# RemoteSch.net
KiCad netlist of a schematic drawn in Altium Designer
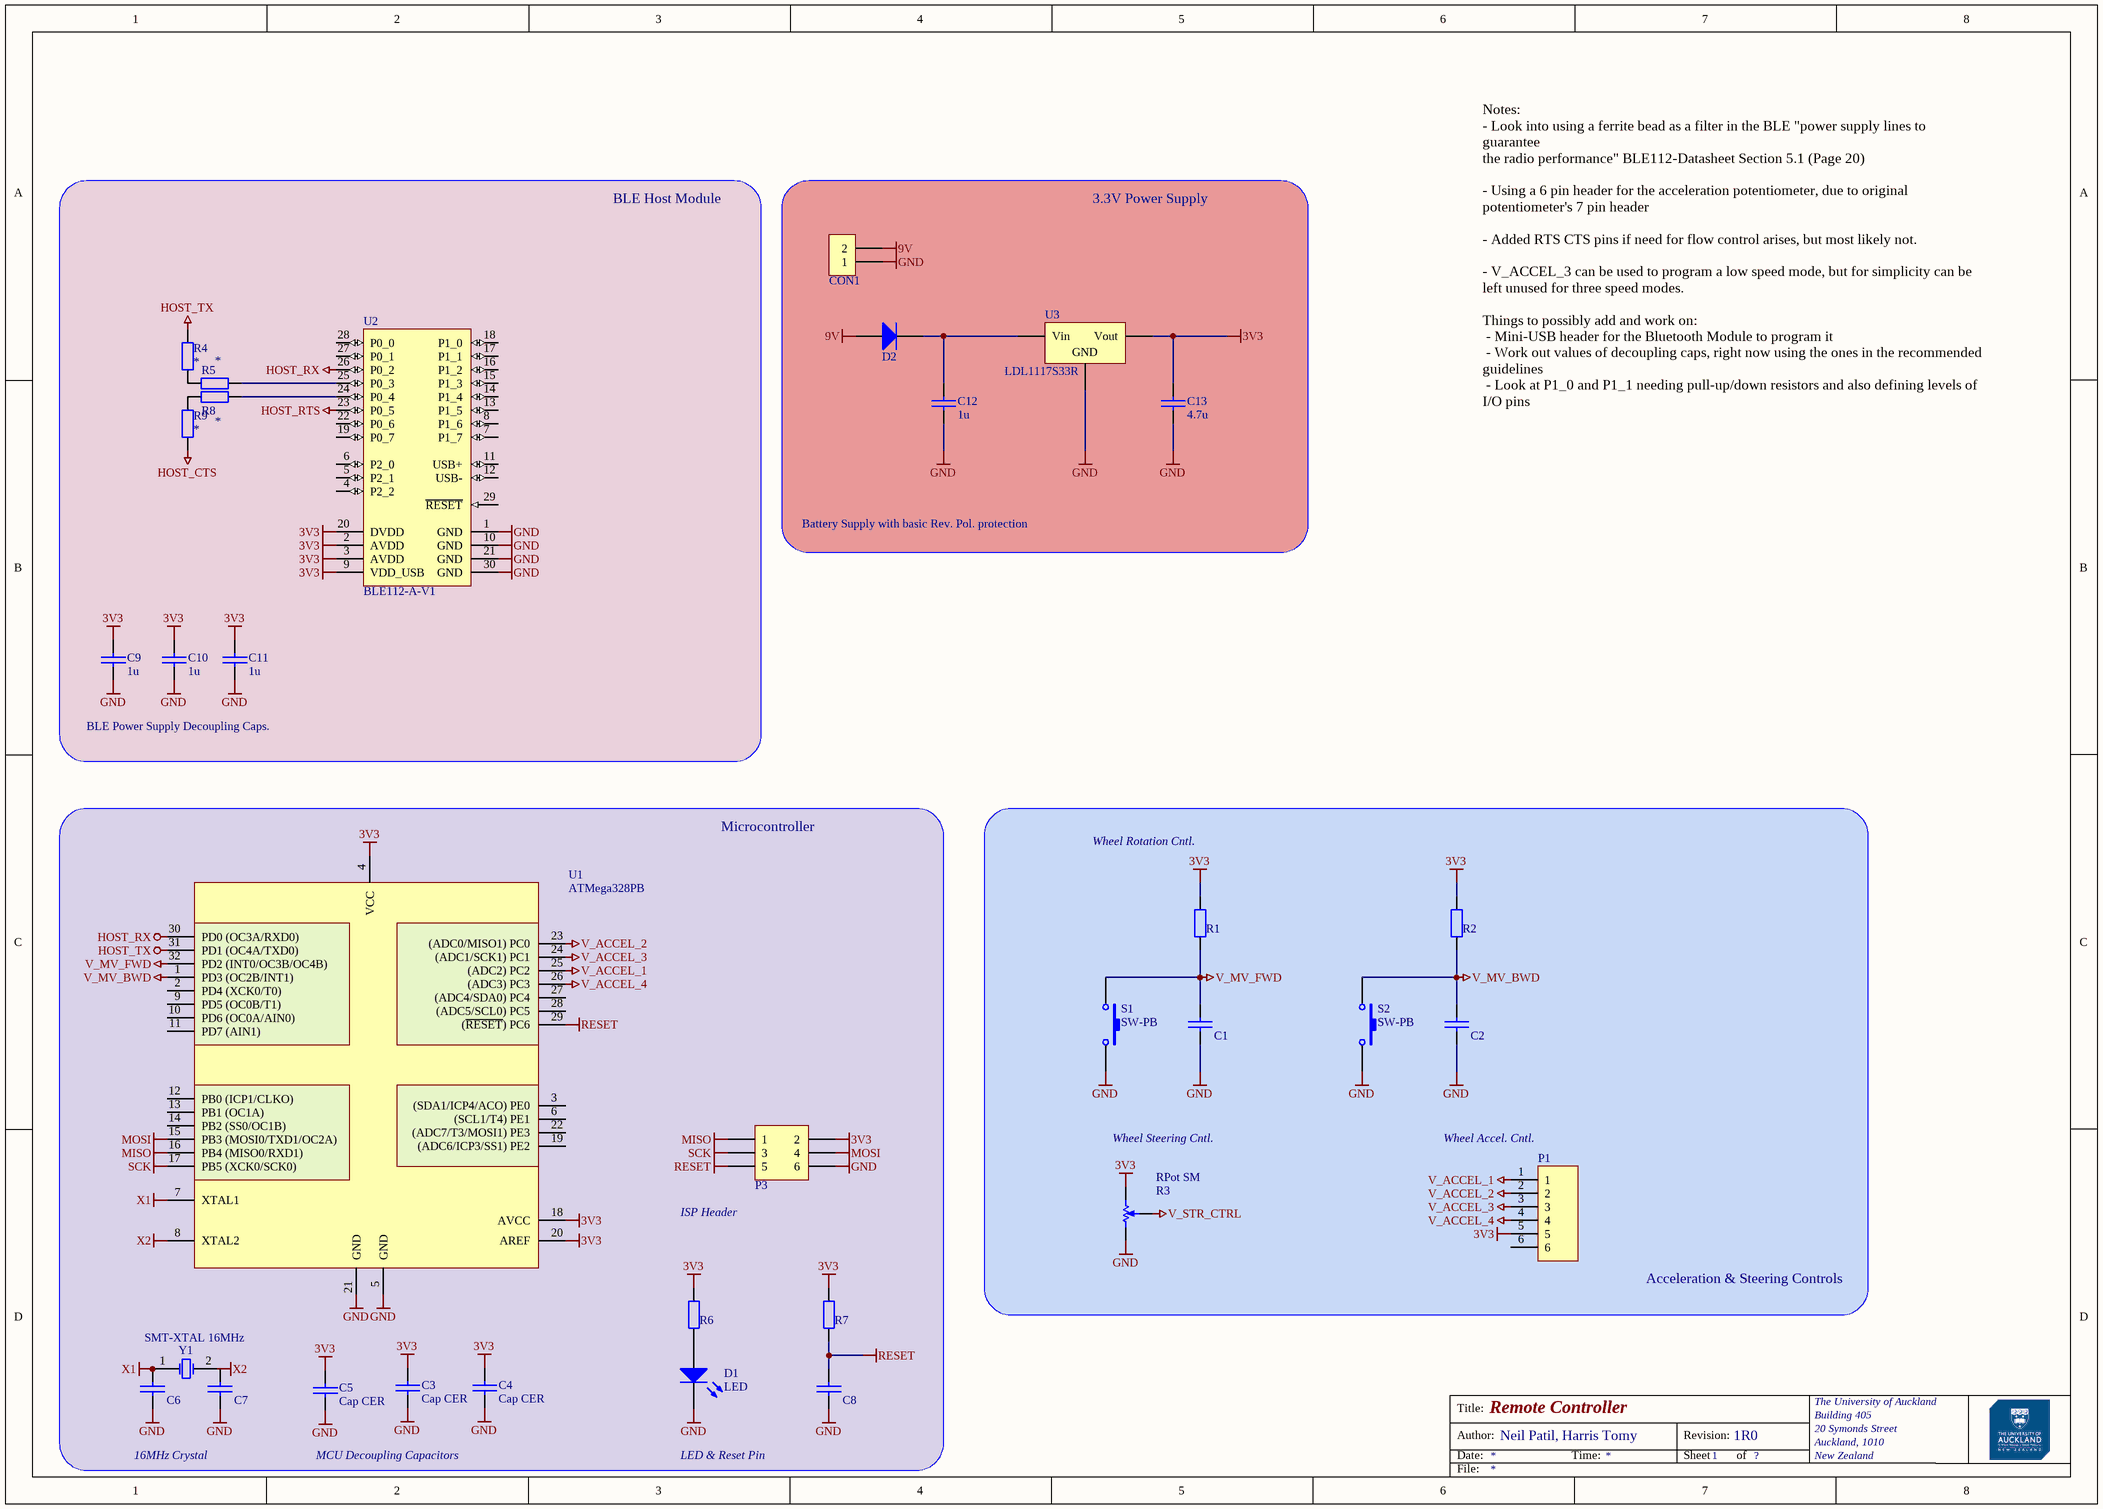
[diagram p0: RemoteSch.SchDoc]

(export (version "E")
  (design (tool "Eeschema 10.0.6"))
  (components
    (comp (ref "C1")
      (value "Capacitor 0805")
      (footprint "C0805")
      (description "CCAP0805")
      (libsource (lib "CommonDevices_V1") (part "CCAP0805"))
    )
    (comp (ref "C2")
      (value "Capacitor 0805")
      (footprint "C0805")
      (description "CCAP0805")
      (libsource (lib "CommonDevices_V1") (part "CCAP0805"))
    )
    (comp (ref "C3")
      (value "Cap CER")
      (footprint "C1206")
      (description "CAP CER 0.1UF 100V C0G 1206")
      (fields (field (name "MPN") "C3216C0G2A104J160AC") (field (name "MANUFACTURER") "TDK Corporation"))
      (libsource (lib "E209_Lib") (part "Cap CER Decoup C3216C0G2A104J160AC"))
    )
    (comp (ref "C4")
      (value "Cap CER")
      (footprint "C1206")
      (description "CAP CER 0.1UF 100V C0G 1206")
      (fields (field (name "MPN") "C3216C0G2A104J160AC") (field (name "MANUFACTURER") "TDK Corporation"))
      (libsource (lib "E209_Lib") (part "Cap CER Decoup C3216C0G2A104J160AC"))
    )
    (comp (ref "C5")
      (value "Cap CER")
      (footprint "C1206")
      (description "CAP CER 0.1UF 100V C0G 1206")
      (fields (field (name "MPN") "C3216C0G2A104J160AC") (field (name "MANUFACTURER") "TDK Corporation"))
      (libsource (lib "E209_Lib") (part "Cap CER Decoup C3216C0G2A104J160AC"))
    )
    (comp (ref "C6")
      (value "CCAP1210")
      (footprint "C1210")
      (fields (field (name "MPN") "?"))
      (libsource (lib "E209_Lib") (part "CCAP1210"))
    )
    (comp (ref "C7")
      (value "CCAP1210")
      (footprint "C1210")
      (fields (field (name "MPN") "?"))
      (libsource (lib "E209_Lib") (part "CCAP1210"))
    )
    (comp (ref "C8")
      (value "CCAP1210")
      (footprint "C1210")
      (libsource (lib "CommonDevices_V1") (part "CCAP1210"))
    )
    (comp (ref "C9")
      (value "1u")
      (footprint "C0805")
      (description "CCAP0805")
      (fields (field (name "MPN") "?") (field (name "Comment") "Capacitor 0805"))
      (libsource (lib "E209_Lib") (part "CCAP0805"))
    )
    (comp (ref "C10")
      (value "1u")
      (footprint "C0805")
      (description "CCAP0805")
      (fields (field (name "MPN") "?") (field (name "Comment") "Capacitor 0805"))
      (libsource (lib "E209_Lib") (part "CCAP0805"))
    )
    (comp (ref "C11")
      (value "1u")
      (footprint "C0805")
      (description "CCAP0805")
      (fields (field (name "MPN") "?") (field (name "Comment") "Capacitor 0805"))
      (libsource (lib "E209_Lib") (part "CCAP0805"))
    )
    (comp (ref "C12")
      (value "1u")
      (footprint "C1210")
      (description "CAP CER 2.2UF 100V X7R 1210")
      (fields (field (name "MPN") "CL32B225KCJSNNE") (field (name "MANUFACTURER") "AVX Corporation"))
      (libsource (lib "E209_Lib") (part "Cap CER HF DC-Link CL32B225KCJSNNE"))
    )
    (comp (ref "C13")
      (value "4.7u")
      (footprint "C1210")
      (description "CAP CER 2.2UF 100V X7R 1210")
      (fields (field (name "MPN") "CL32B225KCJSNNE") (field (name "MANUFACTURER") "AVX Corporation"))
      (libsource (lib "E209_Lib") (part "Cap CER HF DC-Link CL32B225KCJSNNE"))
    )
    (comp (ref "CON1")
      (value "Header 2X1")
      (footprint "HDR2X1_2P54")
      (libsource (lib "CommonDevices_V1") (part "HDR2X1"))
    )
    (comp (ref "D1") (value "LED") (footprint "R0805") (libsource (lib "CommonDevices_V1") (part "LED")))
    (comp (ref "D2") (value "Diode") (footprint "DAX4") (libsource (lib "CommonDevices_V1") (part "Diode")))
    (comp (ref "P1")
      (value "Header 6X1")
      (footprint "HDR6X1_2P54")
      (description "Header, 6-Pin")
      (fields (field (name "PUBLISHER") "Altium Limited"))
      (libsource (lib "CommonDevices_V1") (part "HDR6X1"))
    )
    (comp (ref "P3")
      (value "HDR3X2")
      (footprint "HDR2X3_2P54")
      (description "Header, 3-Pin, Dual row")
      (libsource (lib "CommonDevices_V1") (part "HDR3X2"))
    )
    (comp (ref "R1")
      (value "Resistor 0805")
      (footprint "R0805")
      (description "RES0805")
      (libsource (lib "CommonDevices_V1") (part "RES0805"))
    )
    (comp (ref "R2")
      (value "Resistor 0805")
      (footprint "R0805")
      (description "RES0805")
      (libsource (lib "CommonDevices_V1") (part "RES0805"))
    )
    (comp (ref "R3")
      (value "RPot SM")
      (footprint "POT4MM-2")
      (description "Square Trimming Potentiometer")
      (fields (field (name "PUBLISHER") "Altium Limited"))
      (libsource (lib "Miscellaneous Devices") (part "RPot SM"))
    )
    (comp (ref "R4")
      (value "*")
      (footprint "0805 RES")
      (description "0805 resistor")
      (fields (field (name "PUBLISHER") "Altium Limited"))
      (libsource (lib "") (part "Res_SMT_0805_1"))
    )
    (comp (ref "R5")
      (value "*")
      (footprint "0805 RES")
      (description "0805 resistor")
      (fields (field (name "PUBLISHER") "Altium Limited"))
      (libsource (lib "EE209_Library") (part "Res_SMT_0805"))
    )
    (comp (ref "R6")
      (value "Resistor 1206")
      (footprint "R1206")
      (description "RES1206")
      (libsource (lib "CommonDevices_V1") (part "RES1206"))
    )
    (comp (ref "R7")
      (value "Resistor 1206")
      (footprint "R1206")
      (description "RES1206")
      (libsource (lib "CommonDevices_V1") (part "RES1206"))
    )
    (comp (ref "R8")
      (value "*")
      (footprint "0805 RES")
      (description "0805 resistor")
      (fields (field (name "PUBLISHER") "Altium Limited"))
      (libsource (lib "EE209_Library") (part "Res_SMT_0805"))
    )
    (comp (ref "R9")
      (value "*")
      (footprint "0805 RES")
      (description "0805 resistor")
      (fields (field (name "PUBLISHER") "Altium Limited"))
      (libsource (lib "") (part "Res_SMT_0805_2"))
    )
    (comp (ref "S1")
      (value "SW-PB")
      (footprint "SPST-2")
      (description "Switch")
      (fields (field (name "PUBLISHER") "Altium Limited"))
      (libsource (lib "Miscellaneous Devices") (part "SW-PB"))
    )
    (comp (ref "S2")
      (value "SW-PB")
      (footprint "SPST-2")
      (description "Switch")
      (fields (field (name "PUBLISHER") "Altium Limited"))
      (libsource (lib "Miscellaneous Devices") (part "SW-PB"))
    )
    (comp (ref "U1")
      (value "ATMega328PB")
      (footprint "TQFP32")
      (description "IC MCU 8BIT 32KB FLASH 32TQFP")
      (libsource (lib "CommonDevices_V1") (part "ATMega328PB"))
    )
    (comp (ref "U2")
      (value "BLE112-A-V1")
      (footprint "BLUE-BLE112-A-V1_V")
      (libsource (lib "BLE112") (part "BLE112-A-V1"))
    )
    (comp (ref "U3")
      (value "LDL1117S33R")
      (footprint "SOT223L")
      (description "IC REG LINEAR 3.3V 1.2A SOT223")
      (fields (field (name "MANUFACTURER") "STMicroelectronics"))
      (libsource (lib "E209_Lib") (part "LDO LDL1117S33R"))
    )
    (comp (ref "Y1")
      (value "SMT-XTAL 16MHz")
      (footprint "HC49-US")
      (description "9C-16.000MAAJ-T crystal 16.0000MHZ 18PF SMD")
      (fields
        (field (name "MANUFACTURER") "TXC CORPORATION")
        (field (name "MANUFACTURER PART NUMBER") "9C-16.000MAAJ-T")
      )
      (libsource (lib "EE209_Library") (part "TXC9C-16_XTAL_SMT"))
    )
  )
  (nets
    (net (code "1") (name "3V3") (class "Default")
      (node (ref "C10") (pin "2") (pinfunction "2_2") (pintype "passive"))
      (node (ref "C11") (pin "2") (pinfunction "2_2") (pintype "passive"))
      (node (ref "C13") (pin "2") (pinfunction "2_2") (pintype "passive"))
      (node (ref "C3") (pin "2") (pinfunction "2_2") (pintype "passive"))
      (node (ref "C4") (pin "2") (pinfunction "2_2") (pintype "passive"))
      (node (ref "C5") (pin "2") (pinfunction "2_2") (pintype "passive"))
      (node (ref "C9") (pin "2") (pinfunction "2_2") (pintype "passive"))
      (node (ref "P1") (pin "5") (pinfunction "5_5") (pintype "passive"))
      (node (ref "P3") (pin "2") (pinfunction "2_2") (pintype "passive"))
      (node (ref "R1") (pin "1") (pinfunction "1_1") (pintype "passive"))
      (node (ref "R2") (pin "1") (pinfunction "1_1") (pintype "passive"))
      (node (ref "R3") (pin "CW") (pinfunction "+_CW") (pintype "passive"))
      (node (ref "R6") (pin "2") (pinfunction "2_2") (pintype "passive"))
      (node (ref "R7") (pin "2") (pinfunction "2_2") (pintype "passive"))
      (node (ref "U1") (pin "18") (pinfunction "AVCC_18") (pintype "passive"))
      (node (ref "U1") (pin "20") (pinfunction "AREF_20") (pintype "passive"))
      (node (ref "U1") (pin "4") (pinfunction "VCC_4") (pintype "passive"))
      (node (ref "U2") (pin "2") (pinfunction "AVDD_2") (pintype "power_in"))
      (node (ref "U2") (pin "20") (pinfunction "DVDD_20") (pintype "power_in"))
      (node (ref "U2") (pin "3") (pinfunction "AVDD_3") (pintype "power_in"))
      (node (ref "U2") (pin "9") (pinfunction "VDD_USB_9") (pintype "power_in"))
      (node (ref "U3") (pin "2") (pinfunction "Vout_2") (pintype "passive"))
    )
    (net (code "2") (name "9V") (class "Default")
      (node (ref "CON1") (pin "2") (pinfunction "2_2") (pintype "passive"))
      (node (ref "D2") (pin "1") (pinfunction "1_1") (pintype "passive"))
    )
    (net (code "3") (name "GND") (class "Default")
      (node (ref "C1") (pin "1") (pinfunction "1_1") (pintype "passive"))
      (node (ref "C10") (pin "1") (pinfunction "1_1") (pintype "passive"))
      (node (ref "C11") (pin "1") (pinfunction "1_1") (pintype "passive"))
      (node (ref "C12") (pin "1") (pinfunction "1_1") (pintype "passive"))
      (node (ref "C13") (pin "1") (pinfunction "1_1") (pintype "passive"))
      (node (ref "C2") (pin "1") (pinfunction "1_1") (pintype "passive"))
      (node (ref "C3") (pin "1") (pinfunction "1_1") (pintype "passive"))
      (node (ref "C4") (pin "1") (pinfunction "1_1") (pintype "passive"))
      (node (ref "C5") (pin "1") (pinfunction "1_1") (pintype "passive"))
      (node (ref "C6") (pin "1") (pinfunction "1_1") (pintype "passive"))
      (node (ref "C7") (pin "1") (pinfunction "1_1") (pintype "passive"))
      (node (ref "C8") (pin "1") (pinfunction "1_1") (pintype "passive"))
      (node (ref "C9") (pin "1") (pinfunction "1_1") (pintype "passive"))
      (node (ref "CON1") (pin "1") (pinfunction "1_1") (pintype "passive"))
      (node (ref "D1") (pin "2") (pinfunction "K_2") (pintype "passive"))
      (node (ref "P3") (pin "6") (pinfunction "6_6") (pintype "passive"))
      (node (ref "R3") (pin "CCW") (pinfunction "-_CCW") (pintype "passive"))
      (node (ref "S1") (pin "2") (pinfunction "2_2") (pintype "passive"))
      (node (ref "S2") (pin "2") (pinfunction "2_2") (pintype "passive"))
      (node (ref "U1") (pin "21") (pinfunction "GND_21") (pintype "passive"))
      (node (ref "U1") (pin "5") (pinfunction "GND_5") (pintype "passive"))
      (node (ref "U2") (pin "1") (pinfunction "GND_1") (pintype "power_in"))
      (node (ref "U2") (pin "10") (pinfunction "GND_10") (pintype "power_in"))
      (node (ref "U2") (pin "21") (pinfunction "GND_21") (pintype "power_in"))
      (node (ref "U2") (pin "30") (pinfunction "GND_30") (pintype "power_in"))
      (node (ref "U3") (pin "1") (pinfunction "GND_1") (pintype "passive"))
    )
    (net (code "4") (name "HOST_CTS") (class "Default")
      (node (ref "R9") (pin "1") (pinfunction "1_1") (pintype "passive"))
    )
    (net (code "5") (name "HOST_RTS") (class "Default")
      (node (ref "U2") (pin "23") (pinfunction "P0_5_23") (pintype "bidirectional"))
    )
    (net (code "6") (name "HOST_RX") (class "Default")
      (node (ref "U1") (pin "30") (pinfunction "PD0_(OC3A/RXD0)_30") (pintype "passive"))
      (node (ref "U2") (pin "26") (pinfunction "P0_2_26") (pintype "bidirectional"))
    )
    (net (code "7") (name "HOST_TX") (class "Default")
      (node (ref "R4") (pin "1") (pinfunction "1_1") (pintype "passive"))
      (node (ref "U1") (pin "31") (pinfunction "PD1_(OC4A/TXD0)_31") (pintype "passive"))
    )
    (net (code "8") (name "MISO") (class "Default")
      (node (ref "P3") (pin "1") (pinfunction "1_1") (pintype "passive"))
      (node (ref "U1") (pin "16") (pinfunction "PB4_(MISO0/RXD1)_16") (pintype "passive"))
    )
    (net (code "9") (name "MOSI") (class "Default")
      (node (ref "P3") (pin "4") (pinfunction "4_4") (pintype "passive"))
      (node (ref "U1") (pin "15") (pinfunction "PB3_(MOSI0/TXD1/OC2A)_15") (pintype "passive"))
    )
    (net (code "10") (name "Net-(D1-A)") (class "Default")
      (node (ref "D1") (pin "1") (pinfunction "A_1") (pintype "passive"))
      (node (ref "R6") (pin "1") (pinfunction "1_1") (pintype "passive"))
    )
    (net (code "11") (name "Net-(R4-Pad2)") (class "Default")
      (node (ref "R4") (pin "2") (pinfunction "2_2") (pintype "passive"))
      (node (ref "R5") (pin "1") (pinfunction "1_1") (pintype "passive"))
    )
    (net (code "12") (name "Net-(R8-Pad1)") (class "Default")
      (node (ref "R8") (pin "1") (pinfunction "1_1") (pintype "passive"))
      (node (ref "R9") (pin "2") (pinfunction "2_2") (pintype "passive"))
    )
    (net (code "13") (name "Net-(U2-P0_3)") (class "Default")
      (node (ref "R5") (pin "2") (pinfunction "2_2") (pintype "passive"))
      (node (ref "U2") (pin "25") (pinfunction "P0_3_25") (pintype "bidirectional"))
    )
    (net (code "14") (name "Net-(U2-P0_4)") (class "Default")
      (node (ref "R8") (pin "2") (pinfunction "2_2") (pintype "passive"))
      (node (ref "U2") (pin "24") (pinfunction "P0_4_24") (pintype "bidirectional"))
    )
    (net (code "15") (name "Net-(U3-Vin)") (class "Default")
      (node (ref "C12") (pin "2") (pinfunction "2_2") (pintype "passive"))
      (node (ref "D2") (pin "2") (pinfunction "2_2") (pintype "passive"))
      (node (ref "U3") (pin "3") (pinfunction "Vin_3") (pintype "passive"))
    )
    (net (code "16") (name "Net-(Y1-OSC2)") (class "Default")
      (node (ref "C7") (pin "2") (pinfunction "2_2") (pintype "passive"))
      (node (ref "Y1") (pin "2") (pinfunction "OSC2_2") (pintype "passive"))
    )
    (net (code "17") (name "RESET") (class "Default")
      (node (ref "C8") (pin "2") (pinfunction "2_2") (pintype "passive"))
      (node (ref "P3") (pin "5") (pinfunction "5_5") (pintype "passive"))
      (node (ref "R7") (pin "1") (pinfunction "1_1") (pintype "passive"))
      (node (ref "U1") (pin "29") (pinfunction "(~{RESET})_PC6_29") (pintype "passive"))
    )
    (net (code "18") (name "SCK") (class "Default")
      (node (ref "P3") (pin "3") (pinfunction "3_3") (pintype "passive"))
      (node (ref "U1") (pin "17") (pinfunction "PB5_(XCK0/SCK0)_17") (pintype "passive"))
    )
    (net (code "19") (name "V_ACCEL_1") (class "Default")
      (node (ref "P1") (pin "1") (pinfunction "1_1") (pintype "passive"))
      (node (ref "U1") (pin "25") (pinfunction "(ADC2)_PC2_25") (pintype "passive"))
    )
    (net (code "20") (name "V_ACCEL_2") (class "Default")
      (node (ref "P1") (pin "2") (pinfunction "2_2") (pintype "passive"))
      (node (ref "U1") (pin "23") (pinfunction "(ADC0/MISO1)_PC0_23") (pintype "passive"))
    )
    (net (code "21") (name "V_ACCEL_3") (class "Default")
      (node (ref "P1") (pin "3") (pinfunction "3_3") (pintype "passive"))
      (node (ref "U1") (pin "24") (pinfunction "(ADC1/SCK1)_PC1_24") (pintype "passive"))
    )
    (net (code "22") (name "V_ACCEL_4") (class "Default")
      (node (ref "P1") (pin "4") (pinfunction "4_4") (pintype "passive"))
      (node (ref "U1") (pin "26") (pinfunction "(ADC3)_PC3_26") (pintype "passive"))
    )
    (net (code "23") (name "V_MV_BWD") (class "Default")
      (node (ref "C2") (pin "2") (pinfunction "2_2") (pintype "passive"))
      (node (ref "R2") (pin "2") (pinfunction "2_2") (pintype "passive"))
      (node (ref "S2") (pin "1") (pinfunction "1_1") (pintype "passive"))
      (node (ref "U1") (pin "1") (pinfunction "PD3_(OC2B/INT1)_1") (pintype "passive"))
    )
    (net (code "24") (name "V_MV_FWD") (class "Default")
      (node (ref "C1") (pin "2") (pinfunction "2_2") (pintype "passive"))
      (node (ref "R1") (pin "2") (pinfunction "2_2") (pintype "passive"))
      (node (ref "S1") (pin "1") (pinfunction "1_1") (pintype "passive"))
      (node (ref "U1") (pin "32") (pinfunction "PD2_(INT0/OC3B/OC4B)_32") (pintype "passive"))
    )
    (net (code "25") (name "V_STR_CTRL") (class "Default")
      (node (ref "R3") (pin "W") (pinfunction "W_W") (pintype "passive"))
    )
    (net (code "26") (name "X1") (class "Default")
      (node (ref "C6") (pin "2") (pinfunction "2_2") (pintype "passive"))
      (node (ref "U1") (pin "7") (pinfunction "XTAL1_7") (pintype "passive"))
      (node (ref "Y1") (pin "1") (pinfunction "OSC1_1") (pintype "passive"))
    )
    (net (code "27") (name "X2") (class "Default")
      (node (ref "U1") (pin "8") (pinfunction "XTAL2_8") (pintype "passive"))
    )
    (net (code "28") (name "unconnected-(P1-Pad6)") (class "Default")
      (node (ref "P1") (pin "6") (pinfunction "6_6") (pintype "passive"))
    )
    (net (code "29") (name "unconnected-(U1-(ADC4{slash}SDA0)_PC4-Pad27)") (class "Default")
      (node (ref "U1") (pin "27") (pinfunction "(ADC4/SDA0)_PC4_27") (pintype "passive"))
    )
    (net (code "30") (name "unconnected-(U1-(ADC5{slash}SCL0)_PC5-Pad28)") (class "Default")
      (node (ref "U1") (pin "28") (pinfunction "(ADC5/SCL0)_PC5_28") (pintype "passive"))
    )
    (net (code "31") (name "unconnected-(U1-(ADC6{slash}ICP3{slash}SS1)_PE2-Pad19)") (class "Default")
      (node (ref "U1") (pin "19") (pinfunction "(ADC6/ICP3/SS1)_PE2_19") (pintype "passive"))
    )
    (net (code "32") (name "unconnected-(U1-(ADC7{slash}T3{slash}MOSI1)_PE3-Pad22)") (class "Default")
      (node (ref "U1") (pin "22") (pinfunction "(ADC7/T3/MOSI1)_PE3_22") (pintype "passive"))
    )
    (net (code "33") (name "unconnected-(U1-(SCL1{slash}T4)_PE1-Pad6)") (class "Default")
      (node (ref "U1") (pin "6") (pinfunction "(SCL1/T4)_PE1_6") (pintype "passive"))
    )
    (net (code "34") (name "unconnected-(U1-(SDA1{slash}ICP4{slash}ACO)_PE0-Pad3)") (class "Default")
      (node (ref "U1") (pin "3") (pinfunction "(SDA1/ICP4/ACO)_PE0_3") (pintype "passive"))
    )
    (net (code "35") (name "unconnected-(U1-PB0_(ICP1{slash}CLKO)-Pad12)") (class "Default")
      (node (ref "U1") (pin "12") (pinfunction "PB0_(ICP1/CLKO)_12") (pintype "passive"))
    )
    (net (code "36") (name "unconnected-(U1-PB1_(OC1A)-Pad13)") (class "Default")
      (node (ref "U1") (pin "13") (pinfunction "PB1_(OC1A)_13") (pintype "passive"))
    )
    (net (code "37") (name "unconnected-(U1-PB2_(SS0{slash}OC1B)-Pad14)") (class "Default")
      (node (ref "U1") (pin "14") (pinfunction "PB2_(SS0/OC1B)_14") (pintype "passive"))
    )
    (net (code "38") (name "unconnected-(U1-PD4_(XCK0{slash}T0)-Pad2)") (class "Default")
      (node (ref "U1") (pin "2") (pinfunction "PD4_(XCK0/T0)_2") (pintype "passive"))
    )
    (net (code "39") (name "unconnected-(U1-PD5_(OC0B{slash}T1)-Pad9)") (class "Default")
      (node (ref "U1") (pin "9") (pinfunction "PD5_(OC0B/T1)_9") (pintype "passive"))
    )
    (net (code "40") (name "unconnected-(U1-PD6_(OC0A{slash}AIN0)-Pad10)") (class "Default")
      (node (ref "U1") (pin "10") (pinfunction "PD6_(OC0A/AIN0)_10") (pintype "passive"))
    )
    (net (code "41") (name "unconnected-(U1-PD7_(AIN1)-Pad11)") (class "Default")
      (node (ref "U1") (pin "11") (pinfunction "PD7_(AIN1)_11") (pintype "passive"))
    )
    (net (code "42") (name "unconnected-(U2-P0_0-Pad28)") (class "Default")
      (node (ref "U2") (pin "28") (pinfunction "P0_0_28") (pintype "bidirectional"))
    )
    (net (code "43") (name "unconnected-(U2-P0_1-Pad27)") (class "Default")
      (node (ref "U2") (pin "27") (pinfunction "P0_1_27") (pintype "bidirectional"))
    )
    (net (code "44") (name "unconnected-(U2-P0_6-Pad22)") (class "Default")
      (node (ref "U2") (pin "22") (pinfunction "P0_6_22") (pintype "bidirectional"))
    )
    (net (code "45") (name "unconnected-(U2-P0_7-Pad19)") (class "Default")
      (node (ref "U2") (pin "19") (pinfunction "P0_7_19") (pintype "bidirectional"))
    )
    (net (code "46") (name "unconnected-(U2-P1_0-Pad18)") (class "Default")
      (node (ref "U2") (pin "18") (pinfunction "P1_0_18") (pintype "bidirectional"))
    )
    (net (code "47") (name "unconnected-(U2-P1_1-Pad17)") (class "Default")
      (node (ref "U2") (pin "17") (pinfunction "P1_1_17") (pintype "bidirectional"))
    )
    (net (code "48") (name "unconnected-(U2-P1_2-Pad16)") (class "Default")
      (node (ref "U2") (pin "16") (pinfunction "P1_2_16") (pintype "bidirectional"))
    )
    (net (code "49") (name "unconnected-(U2-P1_3-Pad15)") (class "Default")
      (node (ref "U2") (pin "15") (pinfunction "P1_3_15") (pintype "bidirectional"))
    )
    (net (code "50") (name "unconnected-(U2-P1_4-Pad14)") (class "Default")
      (node (ref "U2") (pin "14") (pinfunction "P1_4_14") (pintype "bidirectional"))
    )
    (net (code "51") (name "unconnected-(U2-P1_5-Pad13)") (class "Default")
      (node (ref "U2") (pin "13") (pinfunction "P1_5_13") (pintype "bidirectional"))
    )
    (net (code "52") (name "unconnected-(U2-P1_6-Pad8)") (class "Default")
      (node (ref "U2") (pin "8") (pinfunction "P1_6_8") (pintype "bidirectional"))
    )
    (net (code "53") (name "unconnected-(U2-P1_7-Pad7)") (class "Default")
      (node (ref "U2") (pin "7") (pinfunction "P1_7_7") (pintype "bidirectional"))
    )
    (net (code "54") (name "unconnected-(U2-P2_0-Pad6)") (class "Default")
      (node (ref "U2") (pin "6") (pinfunction "P2_0_6") (pintype "bidirectional"))
    )
    (net (code "55") (name "unconnected-(U2-P2_1-Pad5)") (class "Default")
      (node (ref "U2") (pin "5") (pinfunction "P2_1_5") (pintype "bidirectional"))
    )
    (net (code "56") (name "unconnected-(U2-P2_2-Pad4)") (class "Default")
      (node (ref "U2") (pin "4") (pinfunction "P2_2_4") (pintype "bidirectional"))
    )
    (net (code "57") (name "unconnected-(U2-USB+-Pad11)") (class "Default")
      (node (ref "U2") (pin "11") (pinfunction "USB+_11") (pintype "bidirectional"))
    )
    (net (code "58") (name "unconnected-(U2-USB--Pad12)") (class "Default")
      (node (ref "U2") (pin "12") (pinfunction "USB-_12") (pintype "bidirectional"))
    )
    (net (code "59") (name "unconnected-(U2-~{RESET}-Pad29)") (class "Default")
      (node (ref "U2") (pin "29") (pinfunction "~{RESET}_29") (pintype "input"))
    )
  )
)
